# RingCenter_v2.net
KiCad netlist of a schematic drawn in EAGLE
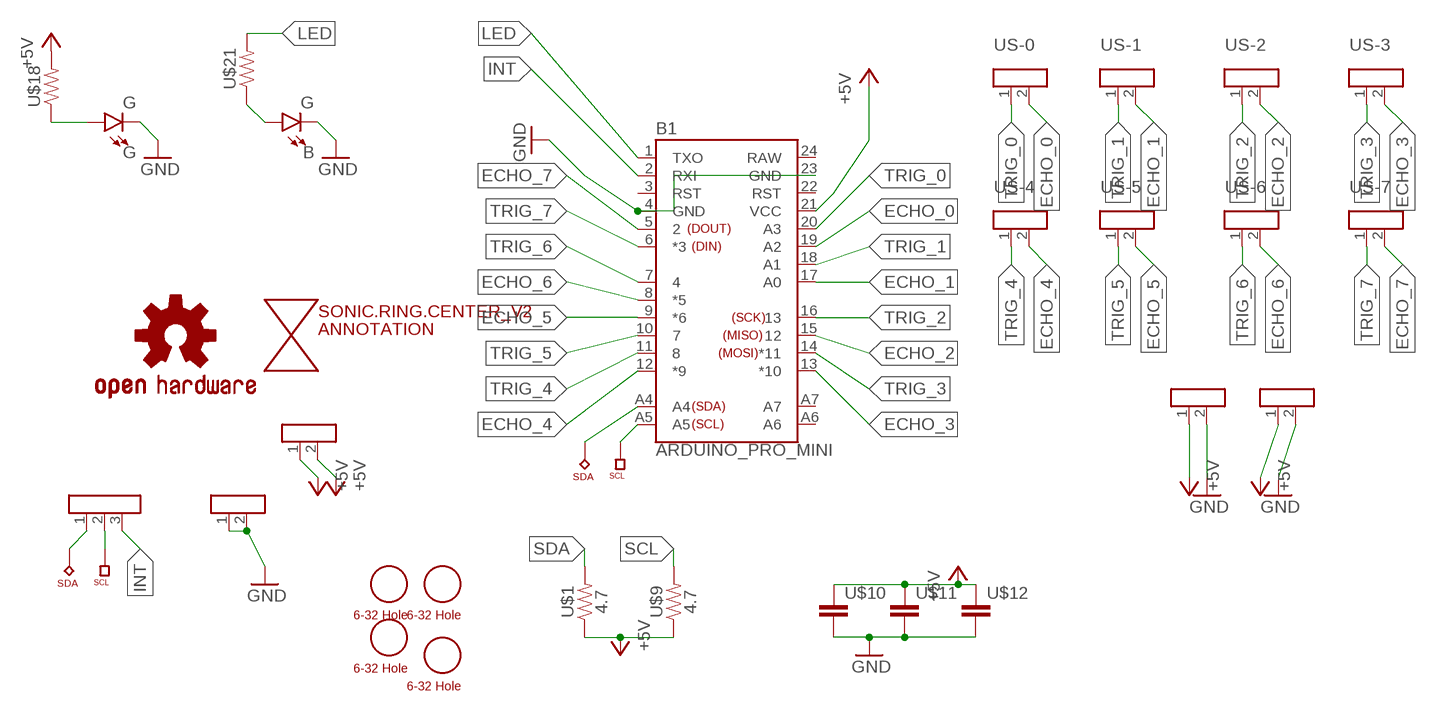
[diagram p0: schematic, sheet 1]

(export (version "E")
  (design (tool "Eeschema 10.0.6"))
  (components
    (comp (ref "B")
      (value "G")
      (footprint "eagle-import:LED_SMD")
      (libsource (lib "eagle-import") (part "LEDSMD"))
    )
    (comp (ref "B1")
      (value "ARDUINO_PRO_MINI")
      (footprint "eagle-import:ARDUINO_PRO_MINI")
      (libsource (lib "eagle-import") (part "ARDUINO_PRO_MINI"))
    )
    (comp (ref "G")
      (value "G")
      (footprint "eagle-import:LED_SMD")
      (libsource (lib "eagle-import") (part "LEDSMD"))
    )
    (comp (ref "LOGO1")
      (value "OSHW-LOGOM")
      (footprint "eagle-import:OSHW-LOGO-M")
      (libsource (lib "eagle-import") (part "OSHW-LOGOM"))
    )
    (comp (ref "SONIC.RING.CENTER_V2")
      (value "ANNOTATION")
      (footprint "eagle-import:ANNOTATION")
      (libsource (lib "eagle-import") (part "ANNOTATION"))
    )
    (comp (ref "U$1")
      (value "4.7")
      (footprint "eagle-import:R1206")
      (libsource (lib "eagle-import") (part "RESISTORSMD"))
    )
    (comp (ref "U$2")
      (value "2XHEADER")
      (footprint "eagle-import:2XHEADER")
      (libsource (lib "eagle-import") (part "2XHEADER"))
    )
    (comp (ref "U$3")
      (value "2XHEADER")
      (footprint "eagle-import:2XHEADER")
      (libsource (lib "eagle-import") (part "2XHEADER"))
    )
    (comp (ref "U$4")
      (value "2XHEADER")
      (footprint "eagle-import:2XHEADER")
      (libsource (lib "eagle-import") (part "2XHEADER"))
    )
    (comp (ref "U$5")
      (value "2XHEADER")
      (footprint "eagle-import:2XHEADER")
      (libsource (lib "eagle-import") (part "2XHEADER"))
    )
    (comp (ref "U$6")
      (value "2XHEADER")
      (footprint "eagle-import:2XHEADER")
      (libsource (lib "eagle-import") (part "2XHEADER"))
    )
    (comp (ref "U$7")
      (value "2XHEADER")
      (footprint "eagle-import:2XHEADER")
      (libsource (lib "eagle-import") (part "2XHEADER"))
    )
    (comp (ref "U$8")
      (value "2XHEADER")
      (footprint "eagle-import:2XHEADER")
      (libsource (lib "eagle-import") (part "2XHEADER"))
    )
    (comp (ref "U$9")
      (value "4.7")
      (footprint "eagle-import:R1206")
      (libsource (lib "eagle-import") (part "RESISTORSMD"))
    )
    (comp (ref "U$10")
      (value "CAP_SMCAP")
      (footprint "eagle-import:C1206")
      (libsource (lib "eagle-import") (part "CAP_SMCAP"))
    )
    (comp (ref "U$11")
      (value "CAP_SMCAP")
      (footprint "eagle-import:C1206")
      (libsource (lib "eagle-import") (part "CAP_SMCAP"))
    )
    (comp (ref "U$12")
      (value "CAP_SMCAP")
      (footprint "eagle-import:C1206")
      (libsource (lib "eagle-import") (part "CAP_SMCAP"))
    )
    (comp (ref "U$13")
      (value "632")
      (footprint "eagle-import:632")
      (libsource (lib "eagle-import") (part "632"))
    )
    (comp (ref "U$14")
      (value "632")
      (footprint "eagle-import:632")
      (libsource (lib "eagle-import") (part "632"))
    )
    (comp (ref "U$15")
      (value "632")
      (footprint "eagle-import:632")
      (libsource (lib "eagle-import") (part "632"))
    )
    (comp (ref "U$16")
      (value "632")
      (footprint "eagle-import:632")
      (libsource (lib "eagle-import") (part "632"))
    )
    (comp (ref "U$17")
      (value "3XHEADER")
      (footprint "eagle-import:3XHEADER")
      (libsource (lib "eagle-import") (part "3XHEADER"))
    )
    (comp (ref "U$18")
      (value "RESISTORSMD")
      (footprint "eagle-import:R1206")
      (libsource (lib "eagle-import") (part "RESISTORSMD"))
    )
    (comp (ref "U$21")
      (value "RESISTORSMD")
      (footprint "eagle-import:R1206")
      (libsource (lib "eagle-import") (part "RESISTORSMD"))
    )
    (comp (ref "US-0")
      (value "2XHEADER")
      (footprint "eagle-import:2XHEADER")
      (libsource (lib "eagle-import") (part "2XHEADER"))
    )
    (comp (ref "US-1")
      (value "2XHEADER")
      (footprint "eagle-import:2XHEADER")
      (libsource (lib "eagle-import") (part "2XHEADER"))
    )
    (comp (ref "US-4")
      (value "2XHEADER")
      (footprint "eagle-import:2XHEADER")
      (libsource (lib "eagle-import") (part "2XHEADER"))
    )
    (comp (ref "US-5")
      (value "2XHEADER")
      (footprint "eagle-import:2XHEADER")
      (libsource (lib "eagle-import") (part "2XHEADER"))
    )
    (comp (ref "US-6")
      (value "2XHEADER")
      (footprint "eagle-import:2XHEADER")
      (libsource (lib "eagle-import") (part "2XHEADER"))
    )
  )
  (nets
    (net (code "1") (name "+5V") (class "Default")
      (node (ref "B1") (pin "21") (pinfunction "VCC_21") (pintype "power_in"))
      (node (ref "U$1") (pin "1") (pinfunction "1_1") (pintype "passive"))
      (node (ref "U$10") (pin "1") (pinfunction "1_1") (pintype "passive"))
      (node (ref "U$11") (pin "1") (pinfunction "1_1") (pintype "passive"))
      (node (ref "U$12") (pin "1") (pinfunction "1_1") (pintype "passive"))
      (node (ref "U$18") (pin "2") (pinfunction "2_2") (pintype "passive"))
      (node (ref "U$9") (pin "1") (pinfunction "1_1") (pintype "passive"))
      (node (ref "US-4") (pin "1") (pinfunction "1_1") (pintype "passive"))
      (node (ref "US-5") (pin "1") (pinfunction "1_1") (pintype "passive"))
      (node (ref "US-6") (pin "1") (pinfunction "1_1") (pintype "passive"))
      (node (ref "US-6") (pin "2") (pinfunction "2_2") (pintype "passive"))
    )
    (net (code "2") (name "/RAW") (class "Default")
      (node (ref "B1") (pin "24") (pinfunction "RAW_24") (pintype "power_in"))
    )
    (net (code "3") (name "ECHO_0") (class "Default")
      (node (ref "B1") (pin "19") (pinfunction "A2_19") (pintype "bidirectional"))
      (node (ref "US-0") (pin "2") (pinfunction "2_2") (pintype "passive"))
    )
    (net (code "4") (name "ECHO_1") (class "Default")
      (node (ref "B1") (pin "17") (pinfunction "A0_17") (pintype "bidirectional"))
      (node (ref "U$8") (pin "2") (pinfunction "2_2") (pintype "passive"))
    )
    (net (code "5") (name "ECHO_2") (class "Default")
      (node (ref "B1") (pin "15") (pinfunction "12_15") (pintype "bidirectional"))
      (node (ref "U$2") (pin "2") (pinfunction "2_2") (pintype "passive"))
    )
    (net (code "6") (name "ECHO_3") (class "Default")
      (node (ref "B1") (pin "13") (pinfunction "*10_13") (pintype "bidirectional"))
      (node (ref "U$7") (pin "2") (pinfunction "2_2") (pintype "passive"))
    )
    (net (code "7") (name "ECHO_4") (class "Default")
      (node (ref "B1") (pin "12") (pinfunction "*9_12") (pintype "bidirectional"))
      (node (ref "U$3") (pin "2") (pinfunction "2_2") (pintype "passive"))
    )
    (net (code "8") (name "ECHO_5") (class "Default")
      (node (ref "B1") (pin "9") (pinfunction "*6_9") (pintype "bidirectional"))
      (node (ref "U$6") (pin "2") (pinfunction "2_2") (pintype "passive"))
    )
    (net (code "9") (name "ECHO_6") (class "Default")
      (node (ref "B1") (pin "8") (pinfunction "*5_8") (pintype "bidirectional"))
      (node (ref "U$4") (pin "2") (pinfunction "2_2") (pintype "passive"))
    )
    (net (code "10") (name "ECHO_7") (class "Default")
      (node (ref "B1") (pin "5") (pinfunction "2_5") (pintype "bidirectional"))
      (node (ref "U$5") (pin "2") (pinfunction "2_2") (pintype "passive"))
    )
    (net (code "11") (name "GND") (class "Default")
      (node (ref "B") (pin "C") (pinfunction "C_C") (pintype "passive"))
      (node (ref "B1") (pin "23") (pinfunction "GND_23") (pintype "power_in"))
      (node (ref "B1") (pin "4") (pinfunction "GND_4") (pintype "power_in"))
      (node (ref "G") (pin "C") (pinfunction "C_C") (pintype "passive"))
      (node (ref "U$10") (pin "2") (pinfunction "2_2") (pintype "passive"))
      (node (ref "U$11") (pin "2") (pinfunction "2_2") (pintype "passive"))
      (node (ref "U$12") (pin "2") (pinfunction "2_2") (pintype "passive"))
      (node (ref "US-1") (pin "1") (pinfunction "1_1") (pintype "passive"))
      (node (ref "US-1") (pin "2") (pinfunction "2_2") (pintype "passive"))
      (node (ref "US-4") (pin "2") (pinfunction "2_2") (pintype "passive"))
      (node (ref "US-5") (pin "2") (pinfunction "2_2") (pintype "passive"))
    )
    (net (code "12") (name "INT") (class "Default")
      (node (ref "B1") (pin "2") (pinfunction "RXI_2") (pintype "bidirectional"))
      (node (ref "U$17") (pin "3") (pinfunction "3_3") (pintype "passive"))
    )
    (net (code "13") (name "LED") (class "Default")
      (node (ref "B1") (pin "1") (pinfunction "TXO_1") (pintype "bidirectional"))
      (node (ref "U$21") (pin "2") (pinfunction "2_2") (pintype "passive"))
    )
    (net (code "14") (name "Net-(B-PadA)") (class "Default")
      (node (ref "B") (pin "A") (pinfunction "A_A") (pintype "passive"))
      (node (ref "U$21") (pin "1") (pinfunction "1_1") (pintype "passive"))
    )
    (net (code "15") (name "Net-(G-PadA)") (class "Default")
      (node (ref "G") (pin "A") (pinfunction "A_A") (pintype "passive"))
      (node (ref "U$18") (pin "1") (pinfunction "1_1") (pintype "passive"))
    )
    (net (code "16") (name "SCL") (class "Default")
      (node (ref "B1") (pin "A5") (pinfunction "A5_A5") (pintype "bidirectional"))
      (node (ref "U$17") (pin "2") (pinfunction "2_2") (pintype "passive"))
      (node (ref "U$9") (pin "2") (pinfunction "2_2") (pintype "passive"))
    )
    (net (code "17") (name "SDA") (class "Default")
      (node (ref "B1") (pin "A4") (pinfunction "A4_A4") (pintype "bidirectional"))
      (node (ref "U$1") (pin "2") (pinfunction "2_2") (pintype "passive"))
      (node (ref "U$17") (pin "1") (pinfunction "1_1") (pintype "passive"))
    )
    (net (code "18") (name "TRIG_0") (class "Default")
      (node (ref "B1") (pin "20") (pinfunction "A3_20") (pintype "bidirectional"))
      (node (ref "US-0") (pin "1") (pinfunction "1_1") (pintype "passive"))
    )
    (net (code "19") (name "TRIG_1") (class "Default")
      (node (ref "B1") (pin "18") (pinfunction "A1_18") (pintype "bidirectional"))
      (node (ref "U$8") (pin "1") (pinfunction "1_1") (pintype "passive"))
    )
    (net (code "20") (name "TRIG_2") (class "Default")
      (node (ref "B1") (pin "16") (pinfunction "13_16") (pintype "bidirectional"))
      (node (ref "U$2") (pin "1") (pinfunction "1_1") (pintype "passive"))
    )
    (net (code "21") (name "TRIG_3") (class "Default")
      (node (ref "B1") (pin "14") (pinfunction "*11_14") (pintype "bidirectional"))
      (node (ref "U$7") (pin "1") (pinfunction "1_1") (pintype "passive"))
    )
    (net (code "22") (name "TRIG_4") (class "Default")
      (node (ref "B1") (pin "11") (pinfunction "8_11") (pintype "bidirectional"))
      (node (ref "U$3") (pin "1") (pinfunction "1_1") (pintype "passive"))
    )
    (net (code "23") (name "TRIG_5") (class "Default")
      (node (ref "B1") (pin "10") (pinfunction "7_10") (pintype "bidirectional"))
      (node (ref "U$6") (pin "1") (pinfunction "1_1") (pintype "passive"))
    )
    (net (code "24") (name "TRIG_6") (class "Default")
      (node (ref "B1") (pin "7") (pinfunction "4_7") (pintype "bidirectional"))
      (node (ref "U$4") (pin "1") (pinfunction "1_1") (pintype "passive"))
    )
    (net (code "25") (name "TRIG_7") (class "Default")
      (node (ref "B1") (pin "6") (pinfunction "*3_6") (pintype "bidirectional"))
      (node (ref "U$5") (pin "1") (pinfunction "1_1") (pintype "passive"))
    )
    (net (code "26") (name "unconnected-(B1-PadA6)") (class "Default")
      (node (ref "B1") (pin "A6") (pinfunction "A6_A6") (pintype "bidirectional"))
    )
    (net (code "27") (name "unconnected-(B1-PadA7)") (class "Default")
      (node (ref "B1") (pin "A7") (pinfunction "A7_A7") (pintype "bidirectional"))
    )
    (net (code "28") (name "unconnected-(B1-RST-Pad3)") (class "Default")
      (node (ref "B1") (pin "3") (pinfunction "RST_3") (pintype "bidirectional"))
    )
    (net (code "29") (name "unconnected-(B1-RST-Pad22)") (class "Default")
      (node (ref "B1") (pin "22") (pinfunction "RST_22") (pintype "bidirectional"))
    )
  )
)
